# Onboard_IO.net
KiCad netlist of a schematic drawn in Altium Designer
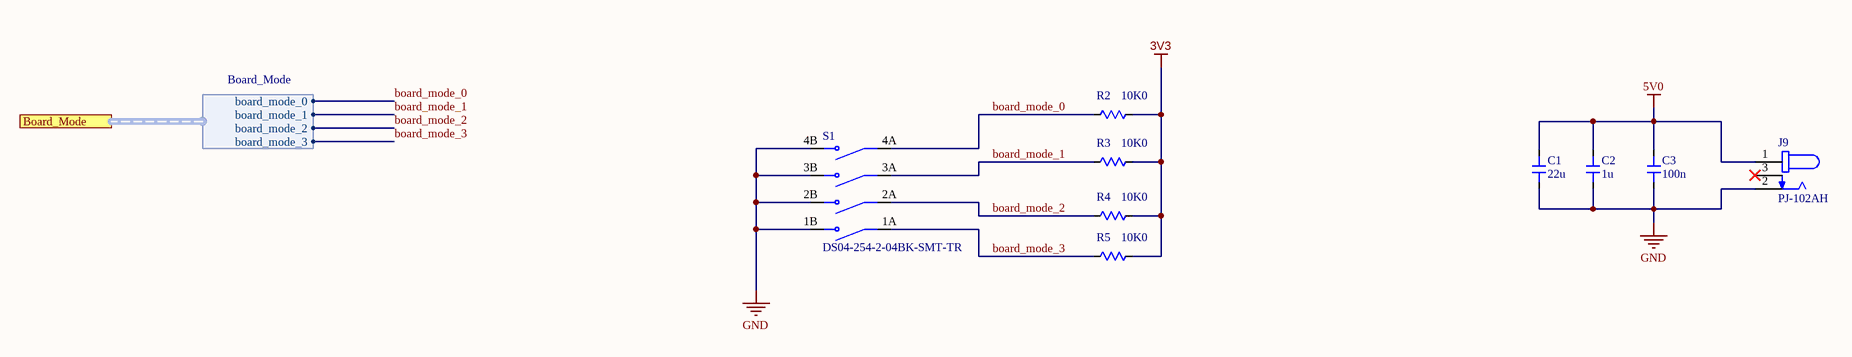
[diagram p0: Onboard_IO.SchDoc]

(export (version "E")
  (design (tool "Eeschema 10.0.6"))
  (components
    (comp (ref "C1")
      (value "22u")
      (footprint "0805_CAPACITOR")
      (description "Capacitor")
      (libsource (lib "UHDEMG") (part "Capacitor"))
    )
    (comp (ref "C2")
      (value "1u")
      (footprint "0603_CAPACITOR")
      (description "Capacitor")
      (libsource (lib "UHDEMG") (part "Capacitor"))
    )
    (comp (ref "C3")
      (value "100n")
      (footprint "0603_CAPACITOR")
      (description "Capacitor")
      (libsource (lib "UHDEMG") (part "Capacitor"))
    )
    (comp (ref "J9")
      (value "PJ-102AH")
      (footprint "CUI_PJ-102AH")
      (description "Power Barrel Connector Jack 2.00mm ID (0.079\"), 5.50mm OD (0.217\") Through Hole, Right Angle")
      (fields (field (name "MF") "Same Sky"))
      (libsource (lib "UHDEMG") (part "CON_PWR_24V_5A"))
    )
    (comp (ref "R2")
      (value "10K0")
      (footprint "0603_RESISTOR")
      (description "Resistor")
      (libsource (lib "UHDEMG") (part "Resistor"))
    )
    (comp (ref "R3")
      (value "10K0")
      (footprint "0603_RESISTOR")
      (description "Resistor")
      (libsource (lib "UHDEMG") (part "Resistor"))
    )
    (comp (ref "R4")
      (value "10K0")
      (footprint "0603_RESISTOR")
      (description "Resistor")
      (libsource (lib "UHDEMG") (part "Resistor"))
    )
    (comp (ref "R5")
      (value "10K0")
      (footprint "0603_RESISTOR")
      (description "Resistor")
      (libsource (lib "UHDEMG") (part "Resistor"))
    )
    (comp (ref "S1")
      (value "DS04-254-2-04BK-SMT-TR")
      (footprint "SW_DS04-254-2-04BK-SMT-TR")
      (description "Dip Switch SPST 4 Position Surface Mount Slide (Standard) Actuator 25mA 24VDC")
      (fields (field (name "MF") "Same Sky"))
      (libsource (lib "UHDEMG") (part "SW_DIP_4_SMT"))
    )
  )
  (nets
    (net (code "2") (name "/board_mode_0") (class "Default")
      (node (ref "R2") (pin "1") (pinfunction "1_1") (pintype "passive"))
      (node (ref "S1") (pin "4A") (pinfunction "COM4_4A") (pintype "passive"))
    )
    (net (code "3") (name "/board_mode_1") (class "Default")
      (node (ref "R3") (pin "1") (pinfunction "1_1") (pintype "passive"))
      (node (ref "S1") (pin "3A") (pinfunction "COM3_3A") (pintype "passive"))
    )
    (net (code "4") (name "/board_mode_2") (class "Default")
      (node (ref "R4") (pin "1") (pinfunction "1_1") (pintype "passive"))
      (node (ref "S1") (pin "2A") (pinfunction "COM2_2A") (pintype "passive"))
    )
    (net (code "5") (name "/board_mode_3") (class "Default")
      (node (ref "R5") (pin "1") (pinfunction "1_1") (pintype "passive"))
      (node (ref "S1") (pin "1A") (pinfunction "COM1_1A") (pintype "passive"))
    )
    (net (code "7") (name "3V3") (class "Default")
      (node (ref "R2") (pin "2") (pinfunction "2_2") (pintype "passive"))
      (node (ref "R3") (pin "2") (pinfunction "2_2") (pintype "passive"))
      (node (ref "R4") (pin "2") (pinfunction "2_2") (pintype "passive"))
      (node (ref "R5") (pin "2") (pinfunction "2_2") (pintype "passive"))
    )
    (net (code "8") (name "5V0") (class "Default")
      (node (ref "C1") (pin "2") (pinfunction "2_2") (pintype "passive"))
      (node (ref "C2") (pin "2") (pinfunction "2_2") (pintype "passive"))
      (node (ref "C3") (pin "2") (pinfunction "2_2") (pintype "passive"))
      (node (ref "J9") (pin "1") (pinfunction "1_1") (pintype "passive"))
    )
    (net (code "9") (name "GND") (class "Default")
      (node (ref "C1") (pin "1") (pinfunction "1_1") (pintype "passive"))
      (node (ref "C2") (pin "1") (pinfunction "1_1") (pintype "passive"))
      (node (ref "C3") (pin "1") (pinfunction "1_1") (pintype "passive"))
      (node (ref "J9") (pin "2") (pinfunction "2_2") (pintype "passive"))
      (node (ref "S1") (pin "1B") (pinfunction "NO1_1B") (pintype "passive"))
      (node (ref "S1") (pin "2B") (pinfunction "NO2_2B") (pintype "passive"))
      (node (ref "S1") (pin "3B") (pinfunction "NO3_3B") (pintype "passive"))
      (node (ref "S1") (pin "4B") (pinfunction "NO4_4B") (pintype "passive"))
    )
    (net (code "10") (name "unconnected-(J9-Pad3)") (class "Default")
      (node (ref "J9") (pin "3") (pinfunction "3_3") (pintype "passive+no_connect"))
    )
  )
)
